# Proyecto.net
KiCad netlist of a schematic drawn in Altium Designer
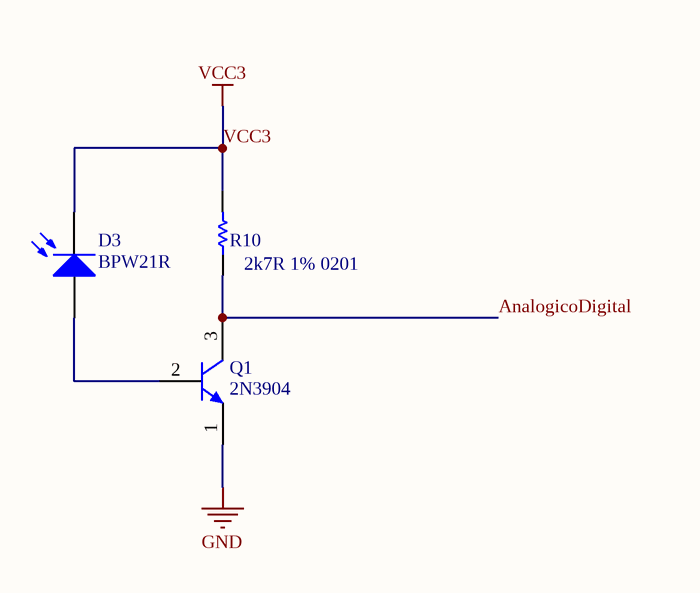
[diagram p0: Proyecto.SchDoc]

(export (version "E")
  (design (tool "Eeschema 10.0.6"))
  (components
    (comp (ref "D3")
      (value "BPW21R")
      (footprint "VISH-BPW21R-2")
      (description "Silicon Photodiode, 565 nm, -40 to 125 degC, 2-Pin TO-5, RoHS, Bulk")
      (fields (field (name "MANUFACTURER") "Vishay"))
      (libsource (lib "Altium Content Vault") (part "DPTO-AK-2"))
    )
    (comp (ref "Q1")
      (value "2N3904")
      (footprint "ONSC-TO-92-3-29-11")
      (description "General Purpose Transistor, NPN Silicon, 200 mA, 60 V, -55 to 150 degC, 3-Pin TO-92, RoHS, Bulk")
      (fields (field (name "MANUFACTURER") "ONSemiconductor"))
      (libsource (lib "Altium Content Vault") (part "BJT-NPN-EBC-3"))
    )
    (comp (ref "R10")
      (value "2k7R 1% 0201")
      (footprint "RESC0201(0603)_M")
      (description "200R 0.05W 1% 0201 (0603 Metric)  SMD")
      (fields (field (name "POWER") "0.05 W") (field (name "TOLERANCE") "1 %"))
      (libsource (lib "Altium Content Vault") (part "CMP-1010-00335-1"))
    )
  )
  (nets
    (net (code "1") (name "/AnalogicoDigital") (class "Default")
      (node (ref "Q1") (pin "3") (pinfunction "C_3") (pintype "passive"))
      (node (ref "R10") (pin "1") (pinfunction "1_1") (pintype "passive"))
    )
    (net (code "2") (name "GND") (class "Default")
      (node (ref "Q1") (pin "1") (pinfunction "E_1") (pintype "passive"))
    )
    (net (code "3") (name "Net-(D3-A)") (class "Default")
      (node (ref "D3") (pin "1") (pinfunction "A_1") (pintype "passive"))
      (node (ref "Q1") (pin "2") (pinfunction "B_2") (pintype "passive"))
    )
    (net (code "4") (name "VCC3") (class "Default")
      (node (ref "D3") (pin "2") (pinfunction "K_2") (pintype "passive"))
      (node (ref "R10") (pin "2") (pinfunction "2_2") (pintype "passive"))
    )
  )
)
